# amplify.net
KiCad netlist of a schematic drawn in Altium Designer
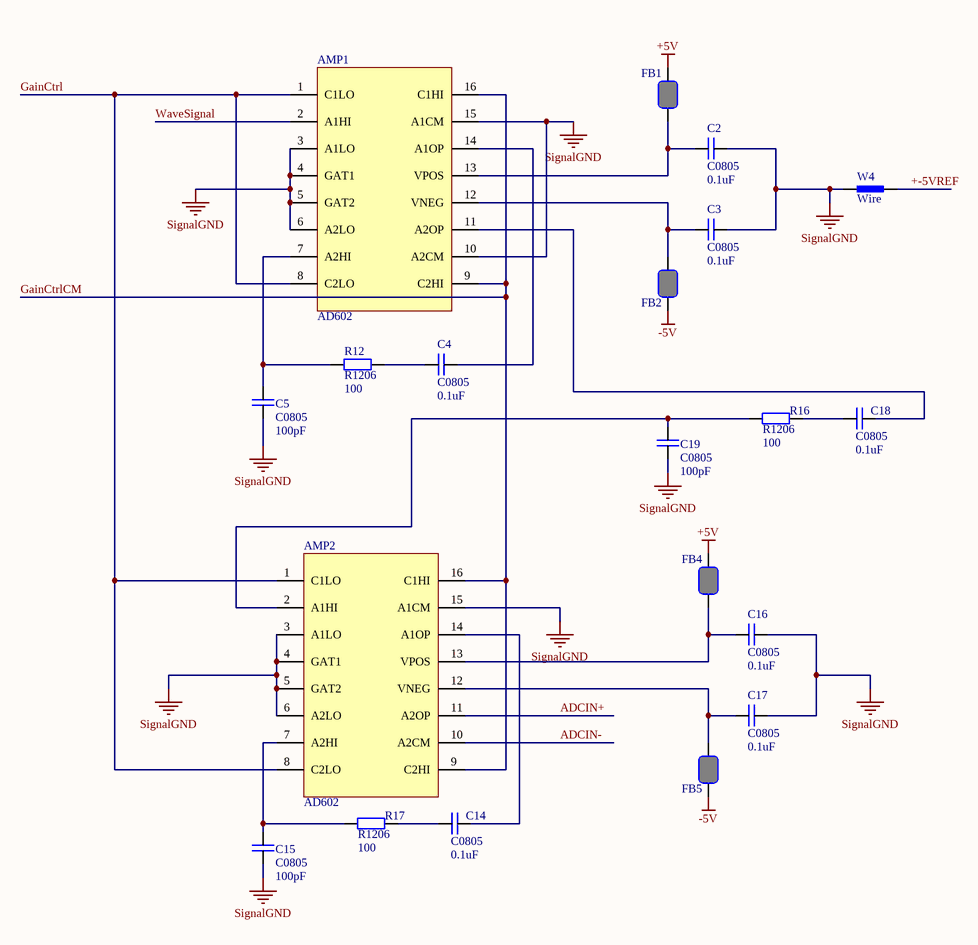
[diagram p0: amplify.SchDoc]

(export (version "E")
  (design (tool "Eeschema 10.0.6"))
  (components
    (comp (ref "AMP1") (value "AD602") (footprint "SOP16") (libsource (lib "UFDLib") (part "AD602")))
    (comp (ref "AMP2") (value "AD602") (footprint "SOP16") (libsource (lib "UFDLib") (part "AD602")))
    (comp (ref "C2")
      (value "C0805")
      (footprint "0805")
      (description "Capacitor, 0805")
      (fields (field (name "ALTIUM_VALUE") "0.1uF"))
      (libsource (lib "UFDLib") (part "C0805"))
    )
    (comp (ref "C3")
      (value "C0805")
      (footprint "0805")
      (description "Capacitor, 0805")
      (fields (field (name "ALTIUM_VALUE") "0.1uF"))
      (libsource (lib "UFDLib") (part "C0805"))
    )
    (comp (ref "C4")
      (value "C0805")
      (footprint "0805")
      (description "Capacitor, 0805")
      (fields (field (name "ALTIUM_VALUE") "0.1uF"))
      (libsource (lib "UFDLib") (part "C0805"))
    )
    (comp (ref "C5")
      (value "C0805")
      (footprint "0805")
      (description "Capacitor, 0805")
      (fields (field (name "ALTIUM_VALUE") "100pF"))
      (libsource (lib "UFDLib") (part "C0805"))
    )
    (comp (ref "C14")
      (value "C0805")
      (footprint "0805")
      (description "Capacitor, 0805")
      (fields (field (name "ALTIUM_VALUE") "0.1uF"))
      (libsource (lib "UFDLib") (part "C0805"))
    )
    (comp (ref "C15")
      (value "C0805")
      (footprint "0805")
      (description "Capacitor, 0805")
      (fields (field (name "ALTIUM_VALUE") "100pF"))
      (libsource (lib "UFDLib") (part "C0805"))
    )
    (comp (ref "C16")
      (value "C0805")
      (footprint "0805")
      (description "Capacitor, 0805")
      (fields (field (name "ALTIUM_VALUE") "0.1uF"))
      (libsource (lib "UFDLib") (part "C0805"))
    )
    (comp (ref "C17")
      (value "C0805")
      (footprint "0805")
      (description "Capacitor, 0805")
      (fields (field (name "ALTIUM_VALUE") "0.1uF"))
      (libsource (lib "UFDLib") (part "C0805"))
    )
    (comp (ref "C18")
      (value "C0805")
      (footprint "0805")
      (description "Capacitor, 0805")
      (fields (field (name "ALTIUM_VALUE") "0.1uF"))
      (libsource (lib "UFDLib") (part "C0805"))
    )
    (comp (ref "C19")
      (value "C0805")
      (footprint "0805")
      (description "Capacitor, 0805")
      (fields (field (name "ALTIUM_VALUE") "100pF"))
      (libsource (lib "UFDLib") (part "C0805"))
    )
    (comp (ref "FB1")
      (value "FB0805")
      (footprint "0805")
      (description "Chip Bead, 0805")
      (libsource (lib "UFDLib") (part "FB0805"))
    )
    (comp (ref "FB2")
      (value "FB0805")
      (footprint "0805")
      (description "Chip Bead, 0805")
      (libsource (lib "UFDLib") (part "FB0805"))
    )
    (comp (ref "FB4")
      (value "FB0805")
      (footprint "0805")
      (description "Chip Bead, 0805")
      (libsource (lib "UFDLib") (part "FB0805"))
    )
    (comp (ref "FB5")
      (value "FB0805")
      (footprint "0805")
      (description "Chip Bead, 0805")
      (libsource (lib "UFDLib") (part "FB0805"))
    )
    (comp (ref "R12")
      (value "R1206")
      (footprint "1206")
      (description "Resistor, 1206, 1/4W")
      (fields (field (name "ALTIUM_VALUE") "100"))
      (libsource (lib "UFDLib") (part "R1206"))
    )
    (comp (ref "R16")
      (value "R1206")
      (footprint "1206")
      (description "Resistor, 1206, 1/4W")
      (fields (field (name "ALTIUM_VALUE") "100"))
      (libsource (lib "UFDLib") (part "R1206"))
    )
    (comp (ref "R17")
      (value "R1206")
      (footprint "1206")
      (description "Resistor, 1206, 1/4W")
      (fields (field (name "ALTIUM_VALUE") "100"))
      (libsource (lib "UFDLib") (part "R1206"))
    )
    (comp (ref "W4") (value "Wire") (footprint "WIRE") (libsource (lib "UFDLib") (part "Wire")))
  )
  (nets
    (net (code "1") (name "+5V") (class "Default")
      (node (ref "FB1") (pin "2") (pinfunction "b_2") (pintype "passive"))
      (node (ref "FB4") (pin "2") (pinfunction "b_2") (pintype "passive"))
    )
    (net (code "2") (name "-5V") (class "Default")
      (node (ref "FB2") (pin "1") (pinfunction "a_1") (pintype "passive"))
      (node (ref "FB5") (pin "1") (pinfunction "a_1") (pintype "passive"))
    )
    (net (code "3") (name "/+-5VREF") (class "Default")
      (node (ref "W4") (pin "2") (pinfunction "b_2") (pintype "passive"))
    )
    (net (code "4") (name "/ADCIN+") (class "Default")
      (node (ref "AMP2") (pin "11") (pinfunction "A2OP_11") (pintype "passive"))
    )
    (net (code "5") (name "/ADCIN-") (class "Default")
      (node (ref "AMP2") (pin "10") (pinfunction "A2CM_10") (pintype "passive"))
    )
    (net (code "6") (name "/GainCtrl") (class "Default")
      (node (ref "AMP1") (pin "1") (pinfunction "C1LO_1") (pintype "passive"))
      (node (ref "AMP1") (pin "8") (pinfunction "C2LO_8") (pintype "passive"))
      (node (ref "AMP2") (pin "1") (pinfunction "C1LO_1") (pintype "passive"))
      (node (ref "AMP2") (pin "8") (pinfunction "C2LO_8") (pintype "passive"))
    )
    (net (code "7") (name "/GainCtrlCM") (class "Default")
      (node (ref "AMP1") (pin "16") (pinfunction "C1HI_16") (pintype "passive"))
      (node (ref "AMP1") (pin "9") (pinfunction "C2HI_9") (pintype "passive"))
      (node (ref "AMP2") (pin "16") (pinfunction "C1HI_16") (pintype "passive"))
      (node (ref "AMP2") (pin "9") (pinfunction "C2HI_9") (pintype "passive"))
    )
    (net (code "8") (name "/WaveSignal") (class "Default")
      (node (ref "AMP1") (pin "2") (pinfunction "A1HI_2") (pintype "passive"))
    )
    (net (code "9") (name "Net-(AMP1-A1OP)") (class "Default")
      (node (ref "AMP1") (pin "14") (pinfunction "A1OP_14") (pintype "passive"))
      (node (ref "C4") (pin "2") (pinfunction "b_2") (pintype "passive"))
    )
    (net (code "10") (name "Net-(AMP1-A2HI)") (class "Default")
      (node (ref "AMP1") (pin "7") (pinfunction "A2HI_7") (pintype "passive"))
      (node (ref "C5") (pin "2") (pinfunction "b_2") (pintype "passive"))
      (node (ref "R12") (pin "1") (pinfunction "a_1") (pintype "passive"))
    )
    (net (code "11") (name "Net-(AMP1-A2OP)") (class "Default")
      (node (ref "AMP1") (pin "11") (pinfunction "A2OP_11") (pintype "passive"))
      (node (ref "C18") (pin "2") (pinfunction "b_2") (pintype "passive"))
    )
    (net (code "12") (name "Net-(AMP1-VNEG)") (class "Default")
      (node (ref "AMP1") (pin "12") (pinfunction "VNEG_12") (pintype "passive"))
      (node (ref "C3") (pin "1") (pinfunction "a_1") (pintype "passive"))
      (node (ref "FB2") (pin "2") (pinfunction "b_2") (pintype "passive"))
    )
    (net (code "13") (name "Net-(AMP1-VPOS)") (class "Default")
      (node (ref "AMP1") (pin "13") (pinfunction "VPOS_13") (pintype "passive"))
      (node (ref "C2") (pin "1") (pinfunction "a_1") (pintype "passive"))
      (node (ref "FB1") (pin "1") (pinfunction "a_1") (pintype "passive"))
    )
    (net (code "14") (name "Net-(AMP2-A1HI)") (class "Default")
      (node (ref "AMP2") (pin "2") (pinfunction "A1HI_2") (pintype "passive"))
      (node (ref "C19") (pin "2") (pinfunction "b_2") (pintype "passive"))
      (node (ref "R16") (pin "1") (pinfunction "a_1") (pintype "passive"))
    )
    (net (code "15") (name "Net-(AMP2-A1OP)") (class "Default")
      (node (ref "AMP2") (pin "14") (pinfunction "A1OP_14") (pintype "passive"))
      (node (ref "C14") (pin "2") (pinfunction "b_2") (pintype "passive"))
    )
    (net (code "16") (name "Net-(AMP2-A2HI)") (class "Default")
      (node (ref "AMP2") (pin "7") (pinfunction "A2HI_7") (pintype "passive"))
      (node (ref "C15") (pin "2") (pinfunction "b_2") (pintype "passive"))
      (node (ref "R17") (pin "1") (pinfunction "a_1") (pintype "passive"))
    )
    (net (code "17") (name "Net-(AMP2-VNEG)") (class "Default")
      (node (ref "AMP2") (pin "12") (pinfunction "VNEG_12") (pintype "passive"))
      (node (ref "C17") (pin "1") (pinfunction "a_1") (pintype "passive"))
      (node (ref "FB5") (pin "2") (pinfunction "b_2") (pintype "passive"))
    )
    (net (code "18") (name "Net-(AMP2-VPOS)") (class "Default")
      (node (ref "AMP2") (pin "13") (pinfunction "VPOS_13") (pintype "passive"))
      (node (ref "C16") (pin "1") (pinfunction "a_1") (pintype "passive"))
      (node (ref "FB4") (pin "1") (pinfunction "a_1") (pintype "passive"))
    )
    (net (code "19") (name "Net-(C4-a)") (class "Default")
      (node (ref "C4") (pin "1") (pinfunction "a_1") (pintype "passive"))
      (node (ref "R12") (pin "2") (pinfunction "b_2") (pintype "passive"))
    )
    (net (code "20") (name "Net-(C14-a)") (class "Default")
      (node (ref "C14") (pin "1") (pinfunction "a_1") (pintype "passive"))
      (node (ref "R17") (pin "2") (pinfunction "b_2") (pintype "passive"))
    )
    (net (code "21") (name "Net-(C18-a)") (class "Default")
      (node (ref "C18") (pin "1") (pinfunction "a_1") (pintype "passive"))
      (node (ref "R16") (pin "2") (pinfunction "b_2") (pintype "passive"))
    )
    (net (code "22") (name "SignalGND") (class "Default")
      (node (ref "AMP1") (pin "10") (pinfunction "A2CM_10") (pintype "passive"))
      (node (ref "AMP1") (pin "15") (pinfunction "A1CM_15") (pintype "passive"))
      (node (ref "AMP1") (pin "3") (pinfunction "A1LO_3") (pintype "passive"))
      (node (ref "AMP1") (pin "4") (pinfunction "GAT1_4") (pintype "passive"))
      (node (ref "AMP1") (pin "5") (pinfunction "GAT2_5") (pintype "passive"))
      (node (ref "AMP1") (pin "6") (pinfunction "A2LO_6") (pintype "passive"))
      (node (ref "AMP2") (pin "15") (pinfunction "A1CM_15") (pintype "passive"))
      (node (ref "AMP2") (pin "3") (pinfunction "A1LO_3") (pintype "passive"))
      (node (ref "AMP2") (pin "4") (pinfunction "GAT1_4") (pintype "passive"))
      (node (ref "AMP2") (pin "5") (pinfunction "GAT2_5") (pintype "passive"))
      (node (ref "AMP2") (pin "6") (pinfunction "A2LO_6") (pintype "passive"))
      (node (ref "C15") (pin "1") (pinfunction "a_1") (pintype "passive"))
      (node (ref "C16") (pin "2") (pinfunction "b_2") (pintype "passive"))
      (node (ref "C17") (pin "2") (pinfunction "b_2") (pintype "passive"))
      (node (ref "C19") (pin "1") (pinfunction "a_1") (pintype "passive"))
      (node (ref "C2") (pin "2") (pinfunction "b_2") (pintype "passive"))
      (node (ref "C3") (pin "2") (pinfunction "b_2") (pintype "passive"))
      (node (ref "C5") (pin "1") (pinfunction "a_1") (pintype "passive"))
      (node (ref "W4") (pin "1") (pinfunction "a_1") (pintype "passive"))
    )
  )
)
